# Power.net
KiCad netlist of a schematic drawn in Altium Designer
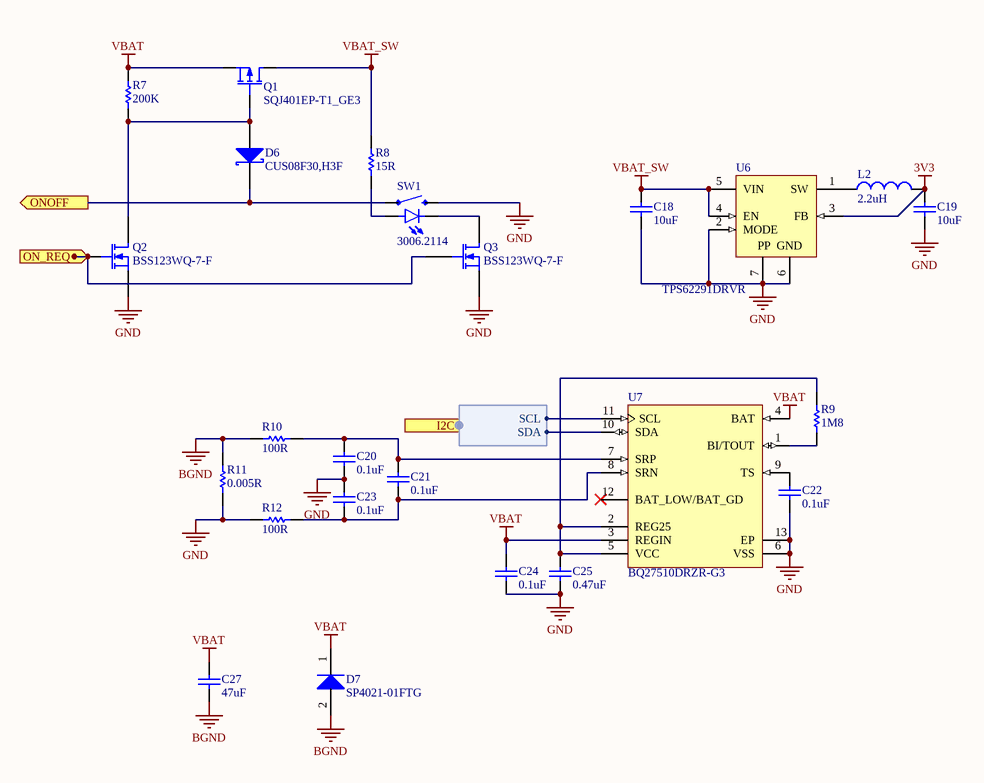
[diagram p0: Power.SchDoc]

(export (version "E")
  (design (tool "Eeschema 10.0.6"))
  (components
    (comp (ref "C18")
      (value "10uF")
      (footprint "C0402[1005X55]")
      (description "10uF 6.3V 20% 0402 (1005 Metric)")
      (fields (field (name "TOLERANCE") "20%") (field (name "PARTNUMBER") "GRM155R60J106ME44D"))
      (libsource (lib "Capacitors") (part "CAP_10uF_6.3V_0402_20%"))
    )
    (comp (ref "C19")
      (value "10uF")
      (footprint "C0402[1005X55]")
      (description "10uF 6.3V 20% 0402 (1005 Metric)")
      (fields (field (name "TOLERANCE") "20%") (field (name "PARTNUMBER") "GRM155R60J106ME44D"))
      (libsource (lib "Capacitors") (part "CAP_10uF_6.3V_0402_20%"))
    )
    (comp (ref "C20")
      (value "0.1uF")
      (footprint "C0402[1005X55]")
      (description "0.1uF 6.3V 10% 0402 (1005 Metric)")
      (fields (field (name "PARTNUMBER") "GRM155R70J104KA01D") (field (name "MANUFACTURER") "Murata"))
      (libsource (lib "Capacitors") (part "CAP_0.1uF_6.3V_0402_10%"))
    )
    (comp (ref "C21")
      (value "0.1uF")
      (footprint "C0402[1005X55]")
      (description "0.1uF 6.3V 10% 0402 (1005 Metric)")
      (fields (field (name "PARTNUMBER") "GRM155R70J104KA01D") (field (name "MANUFACTURER") "Murata"))
      (libsource (lib "Capacitors") (part "CAP_0.1uF_6.3V_0402_10%"))
    )
    (comp (ref "C22")
      (value "0.1uF")
      (footprint "C0402[1005X55]")
      (description "0.1uF 6.3V 10% 0402 (1005 Metric)")
      (fields (field (name "PARTNUMBER") "GRM155R70J104KA01D") (field (name "MANUFACTURER") "Murata"))
      (libsource (lib "Capacitors") (part "CAP_0.1uF_6.3V_0402_10%"))
    )
    (comp (ref "C23")
      (value "0.1uF")
      (footprint "C0402[1005X55]")
      (description "0.1uF 6.3V 10% 0402 (1005 Metric)")
      (fields (field (name "PARTNUMBER") "GRM155R70J104KA01D") (field (name "MANUFACTURER") "Murata"))
      (libsource (lib "Capacitors") (part "CAP_0.1uF_6.3V_0402_10%"))
    )
    (comp (ref "C24")
      (value "0.1uF")
      (footprint "C0402[1005X55]")
      (description "0.1uF 6.3V 10% 0402 (1005 Metric)")
      (fields (field (name "PARTNUMBER") "GRM155R70J104KA01D") (field (name "MANUFACTURER") "Murata"))
      (libsource (lib "Capacitors") (part "CAP_0.1uF_6.3V_0402_10%"))
    )
    (comp (ref "C25")
      (value "0.47uF")
      (footprint "C0402[1005X55]")
      (description "0.47uF 25V 10% 0402 (1005 Metric)")
      (fields (field (name "PARTNUMBER") "GRM155R61E474KE01D") (field (name "MANUFACTURER") "Murata"))
      (libsource (lib "Capacitors") (part "CAP_0.47uF_25V_0402_10%"))
    )
    (comp (ref "C27")
      (value "47uF")
      (footprint "C1206[3216X160]")
      (description "47uF 6.3V 10% 1206 (3216 Metric)")
      (fields (field (name "PARTNUMBER") "GRM31CR60J476KE19L") (field (name "MANUFACTURER") "Murata"))
      (libsource (lib "Capacitors") (part "CAP_47uF_6.3V_1206_10%"))
    )
    (comp (ref "D6")
      (value "CUS08F30,H3F")
      (footprint "SOD-323")
      (fields (field (name "MANUFACTURER") "Toshiba"))
      (libsource (lib "Diodes") (part "CUS08F30,H3F"))
    )
    (comp (ref "D7")
      (value "SP4021-01FTG")
      (footprint "SOD-323")
      (fields (field (name "MANUFACTURER") "Littelfuse"))
      (libsource (lib "Diodes") (part "SP4021-01FTG"))
    )
    (comp (ref "L2")
      (value "2.2uH")
      (footprint "IND0805")
      (description "2.2uH 20% 1.7A 0805")
      (fields (field (name "PARTNUMBER") "LQM21PN2R2MGHL") (field (name "MANUFACTURER") "Murata"))
      (libsource (lib "Inductors") (part "IND_2.2uH_1.7A_0805_20%"))
    )
    (comp (ref "Q1")
      (value "SQJ401EP-T1_GE3")
      (footprint "PowerPak-8")
      (description "P-Channel MOSFET")
      (fields (field (name "MANUFACTURER") "Vishay"))
      (libsource (lib "MOSFETs") (part "SQJ401EP-T1_GE3"))
    )
    (comp (ref "Q2")
      (value "BSS123WQ-7-F")
      (footprint "SOT323-3")
      (description "N-Channel MOSFET")
      (fields (field (name "MANUFACTURER") "Diodes Incorporated"))
      (libsource (lib "MOSFETs") (part "BSS123WQ-7-F"))
    )
    (comp (ref "Q3")
      (value "BSS123WQ-7-F")
      (footprint "SOT323-3")
      (description "N-Channel MOSFET")
      (fields (field (name "MANUFACTURER") "Diodes Incorporated"))
      (libsource (lib "MOSFETs") (part "BSS123WQ-7-F"))
    )
    (comp (ref "R7")
      (value "200K")
      (footprint "R0402[1005]")
      (description "200K 0.063W 1% 0402 (1005 Metric)")
      (fields (field (name "MANUFACTURER") "KOA Speer") (field (name "PARTNUMBER") "RK73H1ETTP2003F"))
      (libsource (lib "Resistors") (part "RES_200K_0402_1%"))
    )
    (comp (ref "R8")
      (value "15R")
      (footprint "R0402[1005]")
      (description "15R 0.063W 1% 0402 (1005 Metric)")
      (fields (field (name "MANUFACTURER") "KOA Speer") (field (name "PARTNUMBER") "RK73H1ETTP15R0F"))
      (libsource (lib "Resistors") (part "RES_15R_0402_1%"))
    )
    (comp (ref "R9")
      (value "1M8")
      (footprint "R0402[1005]")
      (description "1M8 0.063W 1% 0402 (1005 Metric)")
      (fields (field (name "MANUFACTURER") "KOA Speer") (field (name "PARTNUMBER") "RK73H1ETTP1804F"))
      (libsource (lib "Resistors") (part "RES_1M8_0402_1%"))
    )
    (comp (ref "R10")
      (value "100R")
      (footprint "R0402[1005]")
      (description "100R 0.063W 1% 0402 (1005 Metric)")
      (fields (field (name "MANUFACTURER") "KOA Speer") (field (name "PARTNUMBER") "RK73H1ETTP1000F"))
      (libsource (lib "Resistors") (part "RES_100R_0402_1%"))
    )
    (comp (ref "R11")
      (value "0.005R")
      (footprint "R2512[6432]")
      (description "0.005R 2.5W 1% 2512 (6432 Metric)")
      (fields (field (name "MANUFACTURER") "Riedon") (field (name "PARTNUMBER") "CSR2512B0R005F"))
      (libsource (lib "Resistors") (part "RES_0.005R_2512_1%"))
    )
    (comp (ref "R12")
      (value "100R")
      (footprint "R0402[1005]")
      (description "100R 0.063W 1% 0402 (1005 Metric)")
      (fields (field (name "MANUFACTURER") "KOA Speer") (field (name "PARTNUMBER") "RK73H1ETTP1000F"))
      (libsource (lib "Resistors") (part "RES_100R_0402_1%"))
    )
    (comp (ref "SW1")
      (value "3006.2114")
      (footprint "PCBComponent_1")
      (fields (field (name "MANUFACTURER") "Marquadt"))
      (libsource (lib "Components") (part "3006.2114"))
    )
    (comp (ref "U6")
      (value "TPS62291DRVR")
      (footprint "WSON-6")
      (description "Voltage Regulators - Switching Regulators 2.25MHz 1A Step-Down Cnvrtr 3.3V Output")
      (fields (field (name "MANUFACTURER") "Texas Instruments"))
      (libsource (lib "ICs") (part "TPS62291DRVR"))
    )
    (comp (ref "U7")
      (value "BQ27510DRZR-G3")
      (footprint "VSON-12")
      (description "Battery Management System-Side Impedance Track Fuel Gauge")
      (fields (field (name "MANUFACTURER") "Texas Instruments"))
      (libsource (lib "ICs") (part "BQ27510DRZR-G3"))
    )
  )
  (nets
    (net (code "2") (name "/ONOFF") (class "Default")
      (node (ref "D6") (pin "1") (pinfunction "K_1") (pintype "passive"))
      (node (ref "SW1") (pin "1") (pinfunction "1_1") (pintype "passive"))
    )
    (net (code "3") (name "/ON_REQ") (class "Default")
      (node (ref "Q2") (pin "1") (pinfunction "G_1") (pintype "passive"))
      (node (ref "Q3") (pin "1") (pinfunction "G_1") (pintype "passive"))
    )
    (net (code "4") (name "/SCL") (class "Default")
      (node (ref "U7") (pin "11") (pinfunction "SCL_11") (pintype "input"))
    )
    (net (code "5") (name "/SDA") (class "Default")
      (node (ref "U7") (pin "10") (pinfunction "SDA_10") (pintype "bidirectional"))
    )
    (net (code "7") (name "3V3") (class "Default")
      (node (ref "C19") (pin "2") (pinfunction "2_2") (pintype "passive"))
      (node (ref "L2") (pin "2") (pinfunction "2_2") (pintype "passive"))
      (node (ref "U6") (pin "3") (pinfunction "FB_3") (pintype "input"))
    )
    (net (code "8") (name "BGND") (class "Default")
      (node (ref "C27") (pin "1") (pinfunction "1_1") (pintype "passive"))
      (node (ref "D7") (pin "2") (pinfunction "A_2") (pintype "passive"))
      (node (ref "R10") (pin "1") (pinfunction "1_1") (pintype "passive"))
      (node (ref "R11") (pin "2") (pinfunction "2_2") (pintype "passive"))
    )
    (net (code "9") (name "GND") (class "Default")
      (node (ref "C18") (pin "1") (pinfunction "1_1") (pintype "passive"))
      (node (ref "C19") (pin "1") (pinfunction "1_1") (pintype "passive"))
      (node (ref "C20") (pin "1") (pinfunction "1_1") (pintype "passive"))
      (node (ref "C22") (pin "1") (pinfunction "1_1") (pintype "passive"))
      (node (ref "C23") (pin "2") (pinfunction "2_2") (pintype "passive"))
      (node (ref "C24") (pin "1") (pinfunction "1_1") (pintype "passive"))
      (node (ref "C25") (pin "1") (pinfunction "1_1") (pintype "passive"))
      (node (ref "Q2") (pin "2") (pinfunction "S_2") (pintype "passive"))
      (node (ref "Q3") (pin "2") (pinfunction "S_2") (pintype "passive"))
      (node (ref "R11") (pin "1") (pinfunction "1_1") (pintype "passive"))
      (node (ref "R12") (pin "1") (pinfunction "1_1") (pintype "passive"))
      (node (ref "SW1") (pin "2") (pinfunction "2_2") (pintype "passive"))
      (node (ref "U6") (pin "2") (pinfunction "MODE_2") (pintype "input"))
      (node (ref "U6") (pin "6") (pinfunction "GND_6") (pintype "power_in"))
      (node (ref "U6") (pin "7") (pinfunction "EP_7") (pintype "passive"))
      (node (ref "U7") (pin "13") (pinfunction "EP_13") (pintype "passive"))
      (node (ref "U7") (pin "6") (pinfunction "VSS_6") (pintype "power_in"))
    )
    (net (code "10") (name "Net-(D6-A)") (class "Default")
      (node (ref "D6") (pin "2") (pinfunction "A_2") (pintype "passive"))
      (node (ref "Q1") (pin "2") (pinfunction "G_2") (pintype "passive"))
      (node (ref "Q2") (pin "3") (pinfunction "D_3") (pintype "passive"))
      (node (ref "R7") (pin "1") (pinfunction "1_1") (pintype "passive"))
    )
    (net (code "11") (name "Net-(Q3-D)") (class "Default")
      (node (ref "Q3") (pin "3") (pinfunction "D_3") (pintype "passive"))
      (node (ref "SW1") (pin "K") (pinfunction "K_K") (pintype "passive"))
    )
    (net (code "12") (name "Net-(R8-Pad1)") (class "Default")
      (node (ref "R8") (pin "1") (pinfunction "1_1") (pintype "passive"))
      (node (ref "SW1") (pin "A") (pinfunction "A_A") (pintype "passive"))
    )
    (net (code "13") (name "Net-(U6-SW)") (class "Default")
      (node (ref "L2") (pin "1") (pinfunction "1_1") (pintype "passive"))
      (node (ref "U6") (pin "1") (pinfunction "SW_1") (pintype "power_in"))
    )
    (net (code "14") (name "Net-(U7-BI{slash}TOUT)") (class "Default")
      (node (ref "R9") (pin "1") (pinfunction "1_1") (pintype "passive"))
      (node (ref "U7") (pin "1") (pinfunction "BI/TOUT_1") (pintype "bidirectional"))
    )
    (net (code "15") (name "Net-(U7-REG25)") (class "Default")
      (node (ref "C25") (pin "2") (pinfunction "2_2") (pintype "passive"))
      (node (ref "R9") (pin "2") (pinfunction "2_2") (pintype "passive"))
      (node (ref "U7") (pin "2") (pinfunction "REG25_2") (pintype "power_in"))
      (node (ref "U7") (pin "5") (pinfunction "VCC_5") (pintype "power_in"))
    )
    (net (code "16") (name "Net-(U7-SRN)") (class "Default")
      (node (ref "C21") (pin "1") (pinfunction "1_1") (pintype "passive"))
      (node (ref "C23") (pin "1") (pinfunction "1_1") (pintype "passive"))
      (node (ref "R12") (pin "2") (pinfunction "2_2") (pintype "passive"))
      (node (ref "U7") (pin "8") (pinfunction "SRN_8") (pintype "input"))
    )
    (net (code "17") (name "Net-(U7-SRP)") (class "Default")
      (node (ref "C20") (pin "2") (pinfunction "2_2") (pintype "passive"))
      (node (ref "C21") (pin "2") (pinfunction "2_2") (pintype "passive"))
      (node (ref "R10") (pin "2") (pinfunction "2_2") (pintype "passive"))
      (node (ref "U7") (pin "7") (pinfunction "SRP_7") (pintype "input"))
    )
    (net (code "18") (name "Net-(U7-TS)") (class "Default")
      (node (ref "C22") (pin "2") (pinfunction "2_2") (pintype "passive"))
      (node (ref "U7") (pin "9") (pinfunction "TS_9") (pintype "input"))
    )
    (net (code "19") (name "VBAT") (class "Default")
      (node (ref "C24") (pin "2") (pinfunction "2_2") (pintype "passive"))
      (node (ref "C27") (pin "2") (pinfunction "2_2") (pintype "passive"))
      (node (ref "D7") (pin "1") (pinfunction "K_1") (pintype "passive"))
      (node (ref "Q1") (pin "1") (pinfunction "S_1") (pintype "passive"))
      (node (ref "R7") (pin "2") (pinfunction "2_2") (pintype "passive"))
      (node (ref "U7") (pin "3") (pinfunction "REGIN_3") (pintype "power_in"))
      (node (ref "U7") (pin "4") (pinfunction "BAT_4") (pintype "input"))
    )
    (net (code "20") (name "VBAT_SW") (class "Default")
      (node (ref "C18") (pin "2") (pinfunction "2_2") (pintype "passive"))
      (node (ref "Q1") (pin "3") (pinfunction "D_3") (pintype "passive"))
      (node (ref "R8") (pin "2") (pinfunction "2_2") (pintype "passive"))
      (node (ref "U6") (pin "4") (pinfunction "EN_4") (pintype "input"))
      (node (ref "U6") (pin "5") (pinfunction "VIN_5") (pintype "power_in"))
    )
    (net (code "21") (name "unconnected-(U7-BAT_LOW{slash}BAT_GD-Pad12)") (class "Default")
      (node (ref "U7") (pin "12") (pinfunction "BAT_LOW/BAT_GD_12") (pintype "open_collector+no_connect"))
    )
  )
)
